# AUX_power_board_V3_1.net
KiCad netlist of a schematic drawn in EAGLE
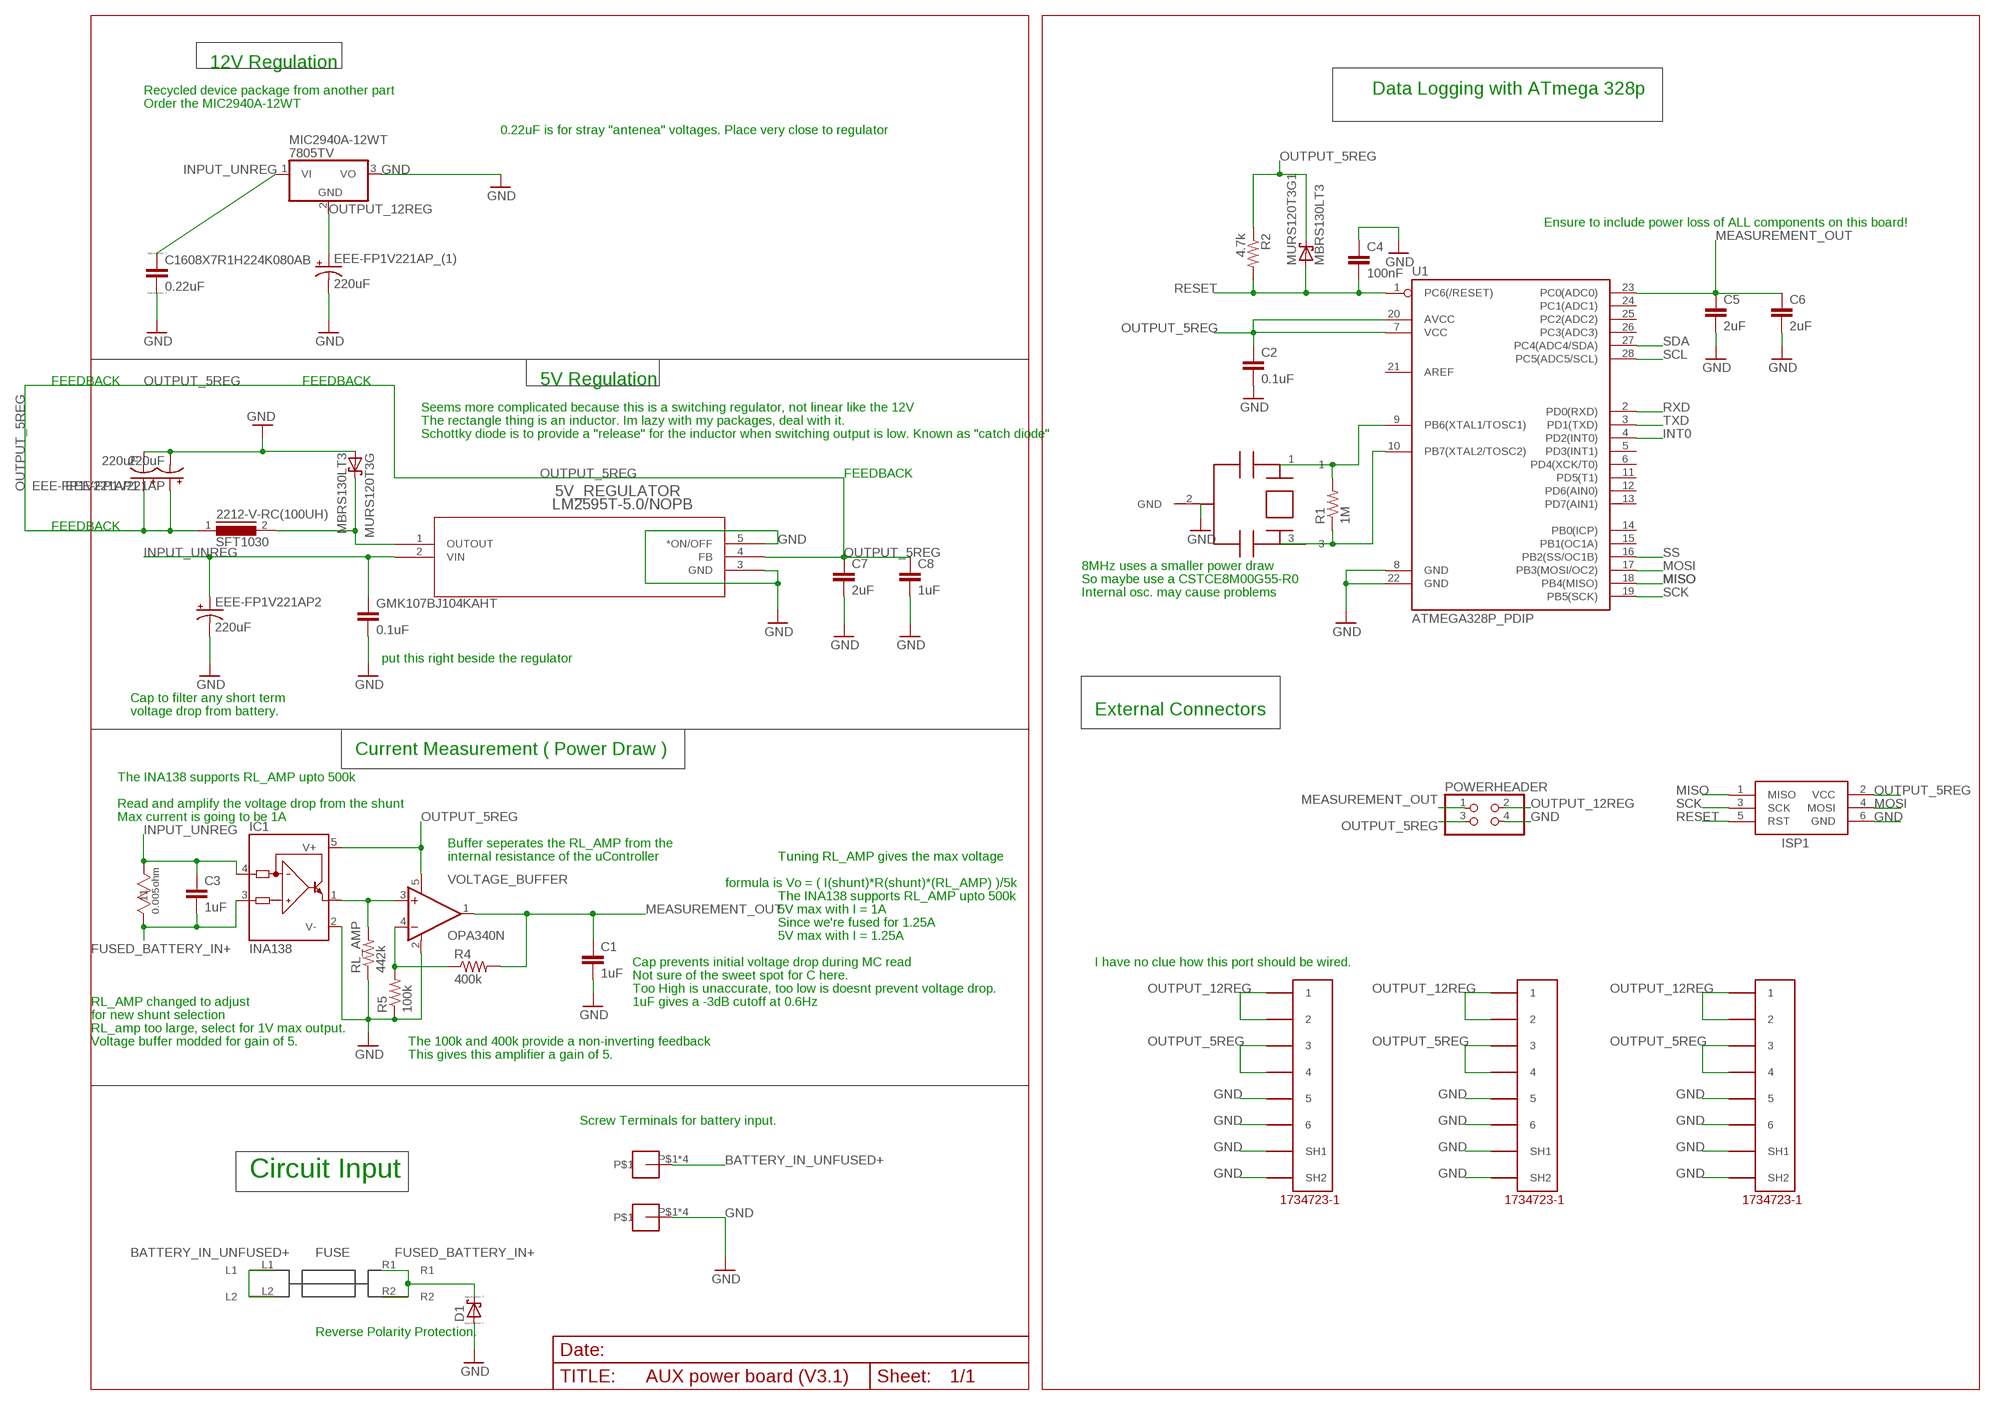
[diagram p0: schematic, sheet 1]

(export (version "E")
  (design (tool "Eeschema 10.0.6"))
  (components
    (comp (ref "5V_REGULATOR")
      (value "LM2595T-5.0/NOPB")
      (footprint "eagle-import:T05D")
      (fields
        (field (name "MANUFACTURER_PART_NUMBER") "LM2595T50")
        (field (name "COPYRIGHT") "Copyright C 2015 Accelerated Designs. All rights reserved")
      )
      (libsource (lib "eagle-import") (part "LM2595T-5.0/NOPB"))
    )
    (comp (ref "15FR005E")
      (value "15FR005E")
      (footprint "eagle-import:RES_15")
      (fields (field (name "COPYRIGHT") "Copyright C 2015 Accelerated Designs. All rights reserved"))
      (libsource (lib "eagle-import") (part "15FR005E"))
    )
    (comp (ref "2212-V-RC(100UH)")
      (value "SFT1030")
      (footprint "eagle-import:SFT1030")
      (libsource (lib "eagle-import") (part "SFT1030"))
    )
    (comp (ref "C1")
      (value "1uF")
      (footprint "eagle-import:C0603")
      (libsource (lib "eagle-import") (part "resistor_C-EUC0603"))
    )
    (comp (ref "C2")
      (value "0.1uF")
      (footprint "eagle-import:C0603")
      (libsource (lib "eagle-import") (part "resistor_C-EUC0603"))
    )
    (comp (ref "C3")
      (value "1uF")
      (footprint "eagle-import:C0603")
      (libsource (lib "eagle-import") (part "C-EUC0603"))
    )
    (comp (ref "C4")
      (value "100nF")
      (footprint "eagle-import:C0603")
      (libsource (lib "eagle-import") (part "C-EUC0603"))
    )
    (comp (ref "C5")
      (value "2uF")
      (footprint "eagle-import:C0603")
      (libsource (lib "eagle-import") (part "C-EUC0603"))
    )
    (comp (ref "C6")
      (value "2uF")
      (footprint "eagle-import:C0603")
      (libsource (lib "eagle-import") (part "C-EUC0603"))
    )
    (comp (ref "C7")
      (value "2uF")
      (footprint "eagle-import:C0603")
      (libsource (lib "eagle-import") (part "C-EUC0603"))
    )
    (comp (ref "C8")
      (value "1uF")
      (footprint "eagle-import:C0603")
      (libsource (lib "eagle-import") (part "C-EUC0603"))
    )
    (comp (ref "C1608X7R1H224K080AB")
      (value "0.22uF")
      (footprint "eagle-import:C0603")
      (libsource (lib "eagle-import") (part "CC0603"))
    )
    (comp (ref "D1")
      (value "SCHOTTKY-DIODESMC")
      (footprint "eagle-import:DIODE_SMC")
      (libsource (lib "eagle-import") (part "SCHOTTKY-DIODESMC"))
    )
    (comp (ref "EEE-FP1V221AP")
      (value "220uF")
      (footprint "eagle-import:175TMP-0808")
      (libsource (lib "eagle-import") (part "CPOL-US175TMP-0808"))
    )
    (comp (ref "EEE-FP1V221AP1")
      (value "220uF")
      (footprint "eagle-import:175TMP-0808")
      (libsource (lib "eagle-import") (part "CPOL-US175TMP-0808"))
    )
    (comp (ref "EEE-FP1V221AP2")
      (value "220uF")
      (footprint "eagle-import:175TMP-0808")
      (libsource (lib "eagle-import") (part "CPOL-US175TMP-0808"))
    )
    (comp (ref "EEE-FP1V221AP_(1)")
      (value "220uF")
      (footprint "eagle-import:175TMP-0808")
      (libsource (lib "eagle-import") (part "CPOL-US175TMP-0808"))
    )
    (comp (ref "GMK107BJ104KAHT")
      (value "0.1uF")
      (footprint "eagle-import:C0603")
      (libsource (lib "eagle-import") (part "C-EUC0603"))
    )
    (comp (ref "IC1")
      (value "INA138")
      (footprint "eagle-import:SOT23-5")
      (fields (field (name "MF") "TEXAS INSTRUMENTS") (field (name "MPN") "INA138NA/250"))
      (libsource (lib "eagle-import") (part "INA138"))
    )
    (comp (ref "ISP1")
      (value "AVRISP-6")
      (footprint "eagle-import:AVRISP")
      (libsource (lib "eagle-import") (part "AVRISP-6"))
    )
    (comp (ref "MIC2940A-12WT")
      (value "7805TV")
      (footprint "eagle-import:TO220V")
      (libsource (lib "eagle-import") (part "78TV05"))
    )
    (comp (ref "MINIBLADE")
      (value "3568")
      (footprint "eagle-import:3568")
      (libsource (lib "eagle-import") (part "3568"))
    )
    (comp (ref "MURS120T3G")
      (value "MBRS130LT3")
      (footprint "eagle-import:SMB")
      (libsource (lib "eagle-import") (part "MBRS130LT3"))
    )
    (comp (ref "MURS120T3G1")
      (value "MBRS130LT3")
      (footprint "eagle-import:SMB")
      (libsource (lib "eagle-import") (part "MBRS130LT3"))
    )
    (comp (ref "POWERHEADER")
      (value "PINHD-2X2")
      (footprint "eagle-import:2X02")
      (libsource (lib "eagle-import") (part "PINHD-2X2"))
    )
    (comp (ref "R1")
      (value "1M")
      (footprint "eagle-import:R0603")
      (libsource (lib "eagle-import") (part "R-US_R0603"))
    )
    (comp (ref "R2")
      (value "4.7k")
      (footprint "eagle-import:R0603")
      (libsource (lib "eagle-import") (part "resistor_R-US_R0603"))
    )
    (comp (ref "R4")
      (value "400k")
      (footprint "eagle-import:R0603")
      (libsource (lib "eagle-import") (part "resistor_R-US_R0603"))
    )
    (comp (ref "R5")
      (value "100k")
      (footprint "eagle-import:R0603")
      (libsource (lib "eagle-import") (part "resistor_R-US_R0603"))
    )
    (comp (ref "RL_AMP")
      (value "442k")
      (footprint "eagle-import:R0603")
      (libsource (lib "eagle-import") (part "resistor_R-US_R0603"))
    )
    (comp (ref "U$1")
      (value "CSTCE16M0V53-R0")
      (footprint "eagle-import:RESONATOR")
      (libsource (lib "eagle-import") (part "CSTCE16M0V53-R0"))
    )
    (comp (ref "U$3")
      (value "5555140-6")
      (footprint "eagle-import:1734723-1_RJ11")
      (libsource (lib "eagle-import") (part "5555140-6"))
    )
    (comp (ref "U$4")
      (value "5555140-6")
      (footprint "eagle-import:1734723-1_RJ11")
      (libsource (lib "eagle-import") (part "5555140-6"))
    )
    (comp (ref "U$5")
      (value "5555140-6")
      (footprint "eagle-import:1734723-1_RJ11")
      (libsource (lib "eagle-import") (part "5555140-6"))
    )
    (comp (ref "U$6")
      (value "SCREW-8191")
      (footprint "eagle-import:SCREW-8191")
      (libsource (lib "eagle-import") (part "SCREW-8191"))
    )
    (comp (ref "U$7")
      (value "SCREW-8191")
      (footprint "eagle-import:SCREW-8191")
      (libsource (lib "eagle-import") (part "SCREW-8191"))
    )
    (comp (ref "U1")
      (value "ATMEGA328P_PDIP")
      (footprint "eagle-import:DIL28-3")
      (libsource (lib "eagle-import") (part "ATMEGA328P_PDIP"))
    )
    (comp (ref "VOLTAGE_BUFFER")
      (value "OPA340N")
      (footprint "eagle-import:SOT23-5")
      (fields (field (name "MPN") "OPA340NA/3KG4"))
      (libsource (lib "eagle-import") (part "OPA340N"))
    )
  )
  (nets
    (net (code "1") (name "/BATTERY_IN_UNFUSED+") (class "Default")
      (node (ref "MINIBLADE") (pin "L1") (pinfunction "L1_L1") (pintype "bidirectional"))
      (node (ref "MINIBLADE") (pin "L2") (pinfunction "L2_L2") (pintype "bidirectional"))
      (node (ref "U$6") (pin "P$1") (pinfunction "P$1_P$1") (pintype "bidirectional"))
      (node (ref "U$6") (pin "P$2") (pinfunction "P$1_P$2") (pintype "bidirectional"))
      (node (ref "U$6") (pin "P$3") (pinfunction "P$1_P$3") (pintype "bidirectional"))
      (node (ref "U$6") (pin "P$4") (pinfunction "P$1_P$4") (pintype "bidirectional"))
    )
    (net (code "2") (name "/FUSED_BATTERY_IN+") (class "Default")
      (node (ref "15FR005E") (pin "1") (pinfunction "11_1") (pintype "passive"))
      (node (ref "C3") (pin "2") (pinfunction "2_2") (pintype "passive"))
      (node (ref "D1") (pin "C") (pinfunction "A_C") (pintype "passive"))
      (node (ref "IC1") (pin "3") (pinfunction "IN+_3") (pintype "input"))
      (node (ref "MINIBLADE") (pin "R1") (pinfunction "R1_R1") (pintype "bidirectional"))
      (node (ref "MINIBLADE") (pin "R2") (pinfunction "R2_R2") (pintype "bidirectional"))
    )
    (net (code "3") (name "/INPUT_UNREG") (class "Default")
      (node (ref "15FR005E") (pin "2") (pinfunction "22_2") (pintype "passive"))
      (node (ref "5V_REGULATOR") (pin "2") (pinfunction "VIN_2") (pintype "input"))
      (node (ref "C1608X7R1H224K080AB") (pin "1") (pinfunction "1_1") (pintype "passive"))
      (node (ref "C3") (pin "1") (pinfunction "1_1") (pintype "passive"))
      (node (ref "EEE-FP1V221AP2") (pin "+") (pinfunction "+_+") (pintype "passive"))
      (node (ref "GMK107BJ104KAHT") (pin "1") (pinfunction "1_1") (pintype "passive"))
      (node (ref "IC1") (pin "4") (pinfunction "IN-_4") (pintype "input"))
      (node (ref "MIC2940A-12WT") (pin "1") (pinfunction "VI_1") (pintype "input"))
    )
    (net (code "4") (name "/INT0") (class "Default")
      (node (ref "U1") (pin "4") (pinfunction "PD2(INT0)_4") (pintype "bidirectional"))
    )
    (net (code "5") (name "/MEASUREMENT_OUT") (class "Default")
      (node (ref "C1") (pin "1") (pinfunction "1_1") (pintype "passive"))
      (node (ref "C5") (pin "1") (pinfunction "1_1") (pintype "passive"))
      (node (ref "C6") (pin "1") (pinfunction "1_1") (pintype "passive"))
      (node (ref "POWERHEADER") (pin "1") (pinfunction "1_1") (pintype "passive"))
      (node (ref "R4") (pin "2") (pinfunction "2_2") (pintype "passive"))
      (node (ref "U1") (pin "23") (pinfunction "PC0(ADC0)_23") (pintype "bidirectional"))
      (node (ref "VOLTAGE_BUFFER") (pin "1") (pinfunction "OUT_1") (pintype "output"))
    )
    (net (code "6") (name "/MISO") (class "Default")
      (node (ref "ISP1") (pin "1") (pinfunction "MISO_1") (pintype "input"))
      (node (ref "U1") (pin "18") (pinfunction "PB4(MISO)_18") (pintype "bidirectional"))
    )
    (net (code "7") (name "/MOSI") (class "Default")
      (node (ref "ISP1") (pin "4") (pinfunction "MOSI_4") (pintype "output"))
      (node (ref "U1") (pin "17") (pinfunction "PB3(MOSI/OC2)_17") (pintype "bidirectional"))
    )
    (net (code "8") (name "/OUTPUT_5REG") (class "Default")
      (node (ref "2212-V-RC(100UH)") (pin "1") (pinfunction "1_1") (pintype "passive"))
      (node (ref "5V_REGULATOR") (pin "4") (pinfunction "FB_4") (pintype "passive"))
      (node (ref "C2") (pin "1") (pinfunction "1_1") (pintype "passive"))
      (node (ref "C7") (pin "1") (pinfunction "1_1") (pintype "passive"))
      (node (ref "C8") (pin "1") (pinfunction "1_1") (pintype "passive"))
      (node (ref "EEE-FP1V221AP") (pin "+") (pinfunction "+_+") (pintype "passive"))
      (node (ref "EEE-FP1V221AP1") (pin "+") (pinfunction "+_+") (pintype "passive"))
      (node (ref "IC1") (pin "5") (pinfunction "V+_5") (pintype "power_in"))
      (node (ref "ISP1") (pin "2") (pinfunction "VCC_2") (pintype "power_in"))
      (node (ref "MURS120T3G1") (pin "C") (pinfunction "C_C") (pintype "passive"))
      (node (ref "POWERHEADER") (pin "3") (pinfunction "3_3") (pintype "passive"))
      (node (ref "R2") (pin "1") (pinfunction "1_1") (pintype "passive"))
      (node (ref "U$3") (pin "3") (pinfunction "3_3") (pintype "bidirectional"))
      (node (ref "U$3") (pin "4") (pinfunction "4_4") (pintype "bidirectional"))
      (node (ref "U$4") (pin "3") (pinfunction "3_3") (pintype "bidirectional"))
      (node (ref "U$4") (pin "4") (pinfunction "4_4") (pintype "bidirectional"))
      (node (ref "U$5") (pin "3") (pinfunction "3_3") (pintype "bidirectional"))
      (node (ref "U$5") (pin "4") (pinfunction "4_4") (pintype "bidirectional"))
      (node (ref "U1") (pin "20") (pinfunction "AVCC_20") (pintype "bidirectional"))
      (node (ref "U1") (pin "7") (pinfunction "VCC_7") (pintype "bidirectional"))
      (node (ref "VOLTAGE_BUFFER") (pin "5") (pinfunction "V+_5") (pintype "power_in"))
    )
    (net (code "9") (name "/OUTPUT_12REG") (class "Default")
      (node (ref "EEE-FP1V221AP_(1)") (pin "+") (pinfunction "+_+") (pintype "passive"))
      (node (ref "MIC2940A-12WT") (pin "2") (pinfunction "GND_2") (pintype "passive"))
      (node (ref "POWERHEADER") (pin "2") (pinfunction "2_2") (pintype "passive"))
      (node (ref "U$3") (pin "1") (pinfunction "1_1") (pintype "bidirectional"))
      (node (ref "U$3") (pin "2") (pinfunction "2_2") (pintype "bidirectional"))
      (node (ref "U$4") (pin "1") (pinfunction "1_1") (pintype "bidirectional"))
      (node (ref "U$4") (pin "2") (pinfunction "2_2") (pintype "bidirectional"))
      (node (ref "U$5") (pin "1") (pinfunction "1_1") (pintype "bidirectional"))
      (node (ref "U$5") (pin "2") (pinfunction "2_2") (pintype "bidirectional"))
    )
    (net (code "10") (name "/RESET") (class "Default")
      (node (ref "C4") (pin "2") (pinfunction "2_2") (pintype "passive"))
      (node (ref "ISP1") (pin "5") (pinfunction "RST_5") (pintype "output"))
      (node (ref "MURS120T3G1") (pin "A") (pinfunction "A_A") (pintype "passive"))
      (node (ref "R2") (pin "2") (pinfunction "2_2") (pintype "passive"))
      (node (ref "U1") (pin "1") (pinfunction "PC6(/RESET)_1") (pintype "bidirectional"))
    )
    (net (code "11") (name "/RXD") (class "Default")
      (node (ref "U1") (pin "2") (pinfunction "PD0(RXD)_2") (pintype "bidirectional"))
    )
    (net (code "12") (name "/SCK") (class "Default")
      (node (ref "ISP1") (pin "3") (pinfunction "SCK_3") (pintype "output"))
      (node (ref "U1") (pin "19") (pinfunction "PB5(SCK)_19") (pintype "bidirectional"))
    )
    (net (code "13") (name "/SCL") (class "Default")
      (node (ref "U1") (pin "28") (pinfunction "PC5(ADC5/SCL)_28") (pintype "bidirectional"))
    )
    (net (code "14") (name "/SDA") (class "Default")
      (node (ref "U1") (pin "27") (pinfunction "PC4(ADC4/SDA)_27") (pintype "bidirectional"))
    )
    (net (code "15") (name "/SS") (class "Default")
      (node (ref "U1") (pin "16") (pinfunction "PB2(SS/OC1B)_16") (pintype "bidirectional"))
    )
    (net (code "16") (name "/TXD") (class "Default")
      (node (ref "U1") (pin "3") (pinfunction "PD1(TXD)_3") (pintype "bidirectional"))
    )
    (net (code "17") (name "GND") (class "Default")
      (node (ref "5V_REGULATOR") (pin "3") (pinfunction "GND_3") (pintype "passive"))
      (node (ref "5V_REGULATOR") (pin "5") (pinfunction "*ON/OFF_5") (pintype "passive"))
      (node (ref "C1") (pin "2") (pinfunction "2_2") (pintype "passive"))
      (node (ref "C1608X7R1H224K080AB") (pin "2") (pinfunction "2_2") (pintype "passive"))
      (node (ref "C2") (pin "2") (pinfunction "2_2") (pintype "passive"))
      (node (ref "C4") (pin "1") (pinfunction "1_1") (pintype "passive"))
      (node (ref "C5") (pin "2") (pinfunction "2_2") (pintype "passive"))
      (node (ref "C6") (pin "2") (pinfunction "2_2") (pintype "passive"))
      (node (ref "C7") (pin "2") (pinfunction "2_2") (pintype "passive"))
      (node (ref "C8") (pin "2") (pinfunction "2_2") (pintype "passive"))
      (node (ref "D1") (pin "A") (pinfunction "C_A") (pintype "passive"))
      (node (ref "EEE-FP1V221AP") (pin "-") (pinfunction "-_-") (pintype "passive"))
      (node (ref "EEE-FP1V221AP1") (pin "-") (pinfunction "-_-") (pintype "passive"))
      (node (ref "EEE-FP1V221AP2") (pin "-") (pinfunction "-_-") (pintype "passive"))
      (node (ref "EEE-FP1V221AP_(1)") (pin "-") (pinfunction "-_-") (pintype "passive"))
      (node (ref "GMK107BJ104KAHT") (pin "2") (pinfunction "2_2") (pintype "passive"))
      (node (ref "IC1") (pin "2") (pinfunction "V-_2") (pintype "power_in"))
      (node (ref "ISP1") (pin "6") (pinfunction "GND_6") (pintype "power_in"))
      (node (ref "MIC2940A-12WT") (pin "3") (pinfunction "VO_3") (pintype "passive"))
      (node (ref "MURS120T3G") (pin "A") (pinfunction "A_A") (pintype "passive"))
      (node (ref "POWERHEADER") (pin "4") (pinfunction "4_4") (pintype "passive"))
      (node (ref "R5") (pin "1") (pinfunction "1_1") (pintype "passive"))
      (node (ref "RL_AMP") (pin "1") (pinfunction "1_1") (pintype "passive"))
      (node (ref "U$1") (pin "2") (pinfunction "GND_2") (pintype "bidirectional"))
      (node (ref "U$3") (pin "5") (pinfunction "5_5") (pintype "bidirectional"))
      (node (ref "U$3") (pin "6") (pinfunction "6_6") (pintype "bidirectional"))
      (node (ref "U$3") (pin "SH1") (pinfunction "SH1_SH1") (pintype "bidirectional"))
      (node (ref "U$3") (pin "SH2") (pinfunction "SH2_SH2") (pintype "bidirectional"))
      (node (ref "U$4") (pin "5") (pinfunction "5_5") (pintype "bidirectional"))
      (node (ref "U$4") (pin "6") (pinfunction "6_6") (pintype "bidirectional"))
      (node (ref "U$4") (pin "SH1") (pinfunction "SH1_SH1") (pintype "bidirectional"))
      (node (ref "U$4") (pin "SH2") (pinfunction "SH2_SH2") (pintype "bidirectional"))
      (node (ref "U$5") (pin "5") (pinfunction "5_5") (pintype "bidirectional"))
      (node (ref "U$5") (pin "6") (pinfunction "6_6") (pintype "bidirectional"))
      (node (ref "U$5") (pin "SH1") (pinfunction "SH1_SH1") (pintype "bidirectional"))
      (node (ref "U$5") (pin "SH2") (pinfunction "SH2_SH2") (pintype "bidirectional"))
      (node (ref "U$7") (pin "P$1") (pinfunction "P$1_P$1") (pintype "bidirectional"))
      (node (ref "U$7") (pin "P$2") (pinfunction "P$1_P$2") (pintype "bidirectional"))
      (node (ref "U$7") (pin "P$3") (pinfunction "P$1_P$3") (pintype "bidirectional"))
      (node (ref "U$7") (pin "P$4") (pinfunction "P$1_P$4") (pintype "bidirectional"))
      (node (ref "U1") (pin "22") (pinfunction "GND_22") (pintype "bidirectional"))
      (node (ref "U1") (pin "8") (pinfunction "GND_8") (pintype "bidirectional"))
      (node (ref "VOLTAGE_BUFFER") (pin "2") (pinfunction "V-_2") (pintype "power_in"))
    )
    (net (code "18") (name "Net-(5V_REGULATOR-OUTOUT)") (class "Default")
      (node (ref "2212-V-RC(100UH)") (pin "2") (pinfunction "2_2") (pintype "passive"))
      (node (ref "5V_REGULATOR") (pin "1") (pinfunction "OUTOUT_1") (pintype "output"))
      (node (ref "MURS120T3G") (pin "C") (pinfunction "C_C") (pintype "passive"))
    )
    (net (code "19") (name "Net-(IC1-OUT)") (class "Default")
      (node (ref "IC1") (pin "1") (pinfunction "OUT_1") (pintype "output"))
      (node (ref "RL_AMP") (pin "2") (pinfunction "2_2") (pintype "passive"))
      (node (ref "VOLTAGE_BUFFER") (pin "3") (pinfunction "+IN_3") (pintype "input"))
    )
    (net (code "20") (name "Net-(U1-PB6(XTAL1{slash}TOSC1))") (class "Default")
      (node (ref "R1") (pin "2") (pinfunction "2_2") (pintype "passive"))
      (node (ref "U$1") (pin "1") (pinfunction "1_1") (pintype "bidirectional"))
      (node (ref "U1") (pin "9") (pinfunction "PB6(XTAL1/TOSC1)_9") (pintype "bidirectional"))
    )
    (net (code "21") (name "Net-(U1-PB7(XTAL2{slash}TOSC2))") (class "Default")
      (node (ref "R1") (pin "1") (pinfunction "1_1") (pintype "passive"))
      (node (ref "U$1") (pin "3") (pinfunction "3_3") (pintype "bidirectional"))
      (node (ref "U1") (pin "10") (pinfunction "PB7(XTAL2/TOSC2)_10") (pintype "bidirectional"))
    )
    (net (code "22") (name "Net-(VOLTAGE_BUFFER--IN)") (class "Default")
      (node (ref "R4") (pin "1") (pinfunction "1_1") (pintype "passive"))
      (node (ref "R5") (pin "2") (pinfunction "2_2") (pintype "passive"))
      (node (ref "VOLTAGE_BUFFER") (pin "4") (pinfunction "-IN_4") (pintype "input"))
    )
    (net (code "23") (name "unconnected-(U1-AREF-Pad21)") (class "Default")
      (node (ref "U1") (pin "21") (pinfunction "AREF_21") (pintype "bidirectional"))
    )
    (net (code "24") (name "unconnected-(U1-PB0(ICP)-Pad14)") (class "Default")
      (node (ref "U1") (pin "14") (pinfunction "PB0(ICP)_14") (pintype "bidirectional"))
    )
    (net (code "25") (name "unconnected-(U1-PB1(OC1A)-Pad15)") (class "Default")
      (node (ref "U1") (pin "15") (pinfunction "PB1(OC1A)_15") (pintype "bidirectional"))
    )
    (net (code "26") (name "unconnected-(U1-PC1(ADC1)-Pad24)") (class "Default")
      (node (ref "U1") (pin "24") (pinfunction "PC1(ADC1)_24") (pintype "bidirectional"))
    )
    (net (code "27") (name "unconnected-(U1-PC2(ADC2)-Pad25)") (class "Default")
      (node (ref "U1") (pin "25") (pinfunction "PC2(ADC2)_25") (pintype "bidirectional"))
    )
    (net (code "28") (name "unconnected-(U1-PC3(ADC3)-Pad26)") (class "Default")
      (node (ref "U1") (pin "26") (pinfunction "PC3(ADC3)_26") (pintype "bidirectional"))
    )
    (net (code "29") (name "unconnected-(U1-PD3(INT1)-Pad5)") (class "Default")
      (node (ref "U1") (pin "5") (pinfunction "PD3(INT1)_5") (pintype "bidirectional"))
    )
    (net (code "30") (name "unconnected-(U1-PD4(XCK{slash}T0)-Pad6)") (class "Default")
      (node (ref "U1") (pin "6") (pinfunction "PD4(XCK/T0)_6") (pintype "bidirectional"))
    )
    (net (code "31") (name "unconnected-(U1-PD5(T1)-Pad11)") (class "Default")
      (node (ref "U1") (pin "11") (pinfunction "PD5(T1)_11") (pintype "bidirectional"))
    )
    (net (code "32") (name "unconnected-(U1-PD6(AIN0)-Pad12)") (class "Default")
      (node (ref "U1") (pin "12") (pinfunction "PD6(AIN0)_12") (pintype "bidirectional"))
    )
    (net (code "33") (name "unconnected-(U1-PD7(AIN1)-Pad13)") (class "Default")
      (node (ref "U1") (pin "13") (pinfunction "PD7(AIN1)_13") (pintype "bidirectional"))
    )
  )
)
